# Seguidor.net
KiCad netlist of a schematic drawn in EAGLE
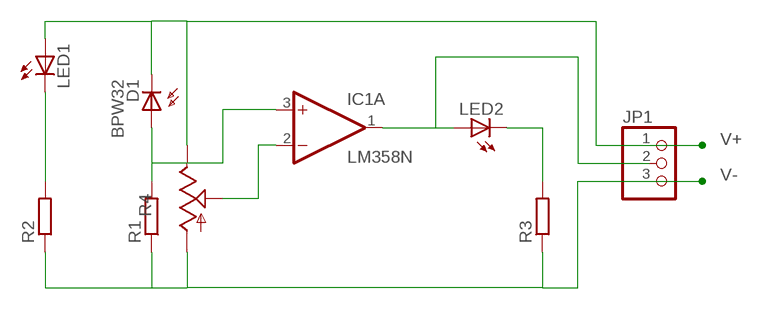
[diagram p0: schematic, sheet 1]

(export (version "E")
  (design (tool "Eeschema 10.0.6"))
  (components
    (comp (ref "D1")
      (value "BPW32")
      (footprint "eagle-import:BPW32")
      (libsource (lib "eagle-import") (part "BPW32"))
    )
    (comp (ref "IC1")
      (value "LM358N")
      (footprint "eagle-import:DIL08")
      (libsource (lib "eagle-import") (part "LM358N"))
    )
    (comp (ref "JP1")
      (value "PINHD-1X3")
      (footprint "eagle-import:1X03")
      (libsource (lib "eagle-import") (part "PINHD-1X3"))
    )
    (comp (ref "LED1")
      (value "LED3MM")
      (footprint "eagle-import:LED3MM")
      (libsource (lib "eagle-import") (part "LED3MM"))
    )
    (comp (ref "LED2")
      (value "LED3MM")
      (footprint "eagle-import:LED3MM")
      (libsource (lib "eagle-import") (part "LED3MM"))
    )
    (comp (ref "R1")
      (value "R-EU_0207/12")
      (footprint "eagle-import:0207_12")
      (libsource (lib "eagle-import") (part "R-EU_0207/12"))
    )
    (comp (ref "R2")
      (value "R-EU_0207/12")
      (footprint "eagle-import:0207_12")
      (libsource (lib "eagle-import") (part "R-EU_0207/12"))
    )
    (comp (ref "R3")
      (value "R-EU_0207/12")
      (footprint "eagle-import:0207_12")
      (libsource (lib "eagle-import") (part "R-EU_0207/12"))
    )
    (comp (ref "R4")
      (value "TRIM_US-B25P")
      (footprint "eagle-import:B25P")
      (libsource (lib "eagle-import") (part "TRIM_US-B25P"))
    )
  )
  (nets
    (net (code "1") (name "/V+") (class "Default")
      (node (ref "D1") (pin "K") (pinfunction "C_K") (pintype "passive"))
      (node (ref "JP1") (pin "1") (pinfunction "1_1") (pintype "passive"))
      (node (ref "LED1") (pin "A") (pinfunction "A_A") (pintype "passive"))
      (node (ref "R4") (pin "E") (pinfunction "E_E") (pintype "passive"))
    )
    (net (code "2") (name "/V-") (class "Default")
      (node (ref "JP1") (pin "3") (pinfunction "3_3") (pintype "passive"))
      (node (ref "R1") (pin "1") (pinfunction "1_1") (pintype "passive"))
      (node (ref "R2") (pin "1") (pinfunction "1_1") (pintype "passive"))
      (node (ref "R3") (pin "1") (pinfunction "1_1") (pintype "passive"))
      (node (ref "R4") (pin "A") (pinfunction "A_A") (pintype "passive"))
    )
    (net (code "3") (name "Net-(IC1A-+IN)") (class "Default")
      (node (ref "D1") (pin "A") (pinfunction "A_A") (pintype "passive"))
      (node (ref "IC1") (pin "3") (pinfunction "+IN_3") (pintype "input"))
      (node (ref "R1") (pin "2") (pinfunction "2_2") (pintype "passive"))
    )
    (net (code "4") (name "Net-(IC1A--IN)") (class "Default")
      (node (ref "IC1") (pin "2") (pinfunction "-IN_2") (pintype "input"))
      (node (ref "R4") (pin "S") (pinfunction "S_S") (pintype "passive"))
    )
    (net (code "5") (name "Net-(IC1A-OUT)") (class "Default")
      (node (ref "IC1") (pin "1") (pinfunction "OUT_1") (pintype "output"))
      (node (ref "JP1") (pin "2") (pinfunction "2_2") (pintype "passive"))
      (node (ref "LED2") (pin "A") (pinfunction "A_A") (pintype "passive"))
    )
    (net (code "6") (name "Net-(LED1-C)") (class "Default")
      (node (ref "LED1") (pin "K") (pinfunction "C_K") (pintype "passive"))
      (node (ref "R2") (pin "2") (pinfunction "2_2") (pintype "passive"))
    )
    (net (code "7") (name "Net-(LED2-C)") (class "Default")
      (node (ref "LED2") (pin "K") (pinfunction "C_K") (pintype "passive"))
      (node (ref "R3") (pin "2") (pinfunction "2_2") (pintype "passive"))
    )
  )
)
